# module.net
KiCad netlist of a schematic drawn in EAGLE
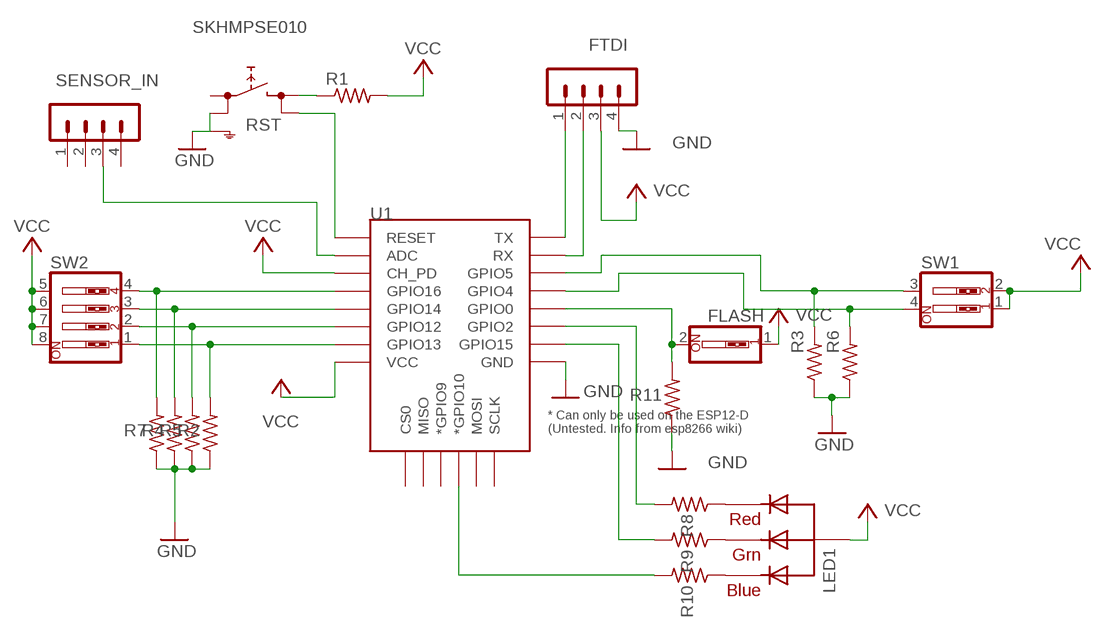
[diagram p0: schematic, sheet 1]

(export (version "E")
  (design (tool "Eeschema 10.0.6"))
  (components
    (comp (ref "FLASH")
      (value "SW_DIP-1")
      (footprint "eagle-import:EDG-01")
      (libsource (lib "eagle-import") (part "SW_DIP-1"))
    )
    (comp (ref "FTDI")
      (value "MA04-1")
      (footprint "eagle-import:MA04-1")
      (libsource (lib "eagle-import") (part "MA04-1"))
    )
    (comp (ref "LED1")
      (value "RGBLED_CA-5MM")
      (footprint "eagle-import:LED5MMRGB")
      (libsource (lib "eagle-import") (part "RGBLED_CA-5MM"))
    )
    (comp (ref "R1")
      (value "R-US_0207/12")
      (footprint "eagle-import:0207_12")
      (libsource (lib "eagle-import") (part "R-US_0207/12"))
    )
    (comp (ref "R2")
      (value "R-US_0207/12")
      (footprint "eagle-import:0207_12")
      (libsource (lib "eagle-import") (part "R-US_0207/12"))
    )
    (comp (ref "R3")
      (value "R-US_0207/12")
      (footprint "eagle-import:0207_12")
      (libsource (lib "eagle-import") (part "R-US_0207/12"))
    )
    (comp (ref "R4")
      (value "R-US_0207/12")
      (footprint "eagle-import:0207_12")
      (libsource (lib "eagle-import") (part "R-US_0207/12"))
    )
    (comp (ref "R5")
      (value "R-US_0207/12")
      (footprint "eagle-import:0207_12")
      (libsource (lib "eagle-import") (part "R-US_0207/12"))
    )
    (comp (ref "R6")
      (value "R-US_0207/12")
      (footprint "eagle-import:0207_12")
      (libsource (lib "eagle-import") (part "R-US_0207/12"))
    )
    (comp (ref "R7")
      (value "R-US_0207/12")
      (footprint "eagle-import:0207_12")
      (libsource (lib "eagle-import") (part "R-US_0207/12"))
    )
    (comp (ref "R8")
      (value "R-US_0207/12")
      (footprint "eagle-import:0207_12")
      (libsource (lib "eagle-import") (part "R-US_0207/12"))
    )
    (comp (ref "R9")
      (value "R-US_0207/12")
      (footprint "eagle-import:0207_12")
      (libsource (lib "eagle-import") (part "R-US_0207/12"))
    )
    (comp (ref "R10")
      (value "R-US_0207/12")
      (footprint "eagle-import:0207_12")
      (libsource (lib "eagle-import") (part "R-US_0207/12"))
    )
    (comp (ref "R11")
      (value "R-US_0207/12")
      (footprint "eagle-import:0207_12")
      (libsource (lib "eagle-import") (part "R-US_0207/12"))
    )
    (comp (ref "RST")
      (value "SKHMPSE010")
      (footprint "eagle-import:SKHMPXE010")
      (libsource (lib "eagle-import") (part "SKHMPE010S"))
    )
    (comp (ref "SENSOR_IN")
      (value "MA04-1")
      (footprint "eagle-import:MA04-1")
      (libsource (lib "eagle-import") (part "MA04-1"))
    )
    (comp (ref "SW1")
      (value "SW_DIP-2")
      (footprint "eagle-import:EDG-02")
      (libsource (lib "eagle-import") (part "SW_DIP-2"))
    )
    (comp (ref "SW2")
      (value "SW_DIP-4")
      (footprint "eagle-import:EDG-04")
      (libsource (lib "eagle-import") (part "SW_DIP-4"))
    )
    (comp (ref "U1")
      (value "ESP12ESMD")
      (footprint "eagle-import:ESP12E-SMD")
      (libsource (lib "eagle-import") (part "ESP12ESMD"))
    )
  )
  (nets
    (net (code "1") (name "GND") (class "Default")
      (node (ref "FTDI") (pin "4") (pinfunction "4_4") (pintype "passive"))
      (node (ref "R11") (pin "1") (pinfunction "1_1") (pintype "passive"))
      (node (ref "R2") (pin "1") (pinfunction "1_1") (pintype "passive"))
      (node (ref "R3") (pin "1") (pinfunction "1_1") (pintype "passive"))
      (node (ref "R4") (pin "1") (pinfunction "1_1") (pintype "passive"))
      (node (ref "R5") (pin "1") (pinfunction "1_1") (pintype "passive"))
      (node (ref "R6") (pin "1") (pinfunction "1_1") (pintype "passive"))
      (node (ref "R7") (pin "1") (pinfunction "1_1") (pintype "passive"))
      (node (ref "RST") (pin "2") (pinfunction "1.2_2") (pintype "passive"))
      (node (ref "RST") (pin "5") (pinfunction "SH_5") (pintype "passive"))
      (node (ref "U1") (pin "GND") (pinfunction "GND_GND") (pintype "bidirectional"))
    )
    (net (code "2") (name "Net-(FLASH-Pad2)") (class "Default")
      (node (ref "FLASH") (pin "2") (pinfunction "2_2") (pintype "passive"))
      (node (ref "R11") (pin "2") (pinfunction "2_2") (pintype "passive"))
      (node (ref "U1") (pin "GPIO0") (pinfunction "GPIO0_GPIO0") (pintype "bidirectional"))
    )
    (net (code "3") (name "Net-(LED1-BLUE)") (class "Default")
      (node (ref "LED1") (pin "4") (pinfunction "BLUE_4") (pintype "bidirectional"))
      (node (ref "R10") (pin "1") (pinfunction "1_1") (pintype "passive"))
    )
    (net (code "4") (name "Net-(LED1-GREEN)") (class "Default")
      (node (ref "LED1") (pin "3") (pinfunction "GREEN_3") (pintype "bidirectional"))
      (node (ref "R9") (pin "1") (pinfunction "1_1") (pintype "passive"))
    )
    (net (code "5") (name "Net-(LED1-RED)") (class "Default")
      (node (ref "LED1") (pin "1") (pinfunction "RED_1") (pintype "bidirectional"))
      (node (ref "R8") (pin "1") (pinfunction "1_1") (pintype "passive"))
    )
    (net (code "6") (name "Net-(R2-Pad2)") (class "Default")
      (node (ref "R2") (pin "2") (pinfunction "2_2") (pintype "passive"))
      (node (ref "SW2") (pin "1") (pinfunction "1_1") (pintype "passive"))
      (node (ref "U1") (pin "GPIO13") (pinfunction "GPIO13_GPIO13") (pintype "bidirectional"))
    )
    (net (code "7") (name "Net-(R3-Pad2)") (class "Default")
      (node (ref "R3") (pin "2") (pinfunction "2_2") (pintype "passive"))
      (node (ref "SW1") (pin "3") (pinfunction "3_3") (pintype "passive"))
      (node (ref "U1") (pin "GPIO5") (pinfunction "GPIO5_GPIO5") (pintype "bidirectional"))
    )
    (net (code "8") (name "Net-(R4-Pad2)") (class "Default")
      (node (ref "R4") (pin "2") (pinfunction "2_2") (pintype "passive"))
      (node (ref "SW2") (pin "3") (pinfunction "3_3") (pintype "passive"))
      (node (ref "U1") (pin "GPIO14") (pinfunction "GPIO14_GPIO14") (pintype "bidirectional"))
    )
    (net (code "9") (name "Net-(R5-Pad2)") (class "Default")
      (node (ref "R5") (pin "2") (pinfunction "2_2") (pintype "passive"))
      (node (ref "SW2") (pin "2") (pinfunction "2_2") (pintype "passive"))
      (node (ref "U1") (pin "GPIO12") (pinfunction "GPIO12_GPIO12") (pintype "bidirectional"))
    )
    (net (code "10") (name "Net-(R6-Pad2)") (class "Default")
      (node (ref "R6") (pin "2") (pinfunction "2_2") (pintype "passive"))
      (node (ref "SW1") (pin "4") (pinfunction "4_4") (pintype "passive"))
      (node (ref "U1") (pin "GPIO4") (pinfunction "GPIO4_GPIO4") (pintype "bidirectional"))
    )
    (net (code "11") (name "Net-(R7-Pad2)") (class "Default")
      (node (ref "R7") (pin "2") (pinfunction "2_2") (pintype "passive"))
      (node (ref "SW2") (pin "4") (pinfunction "4_4") (pintype "passive"))
      (node (ref "U1") (pin "GPIO16") (pinfunction "GPIO16_GPIO16") (pintype "bidirectional"))
    )
    (net (code "12") (name "Net-(R8-Pad2)") (class "Default")
      (node (ref "R8") (pin "2") (pinfunction "2_2") (pintype "passive"))
      (node (ref "U1") (pin "GPIO2") (pinfunction "GPIO2_GPIO2") (pintype "bidirectional"))
    )
    (net (code "13") (name "Net-(R9-Pad2)") (class "Default")
      (node (ref "R9") (pin "2") (pinfunction "2_2") (pintype "passive"))
      (node (ref "U1") (pin "GPIO15") (pinfunction "GPIO15_GPIO15") (pintype "bidirectional"))
    )
    (net (code "14") (name "Net-(RST-2.1)") (class "Default")
      (node (ref "R1") (pin "1") (pinfunction "1_1") (pintype "passive"))
      (node (ref "RST") (pin "3") (pinfunction "2.1_3") (pintype "passive"))
    )
    (net (code "15") (name "Net-(RST-2.2)") (class "Default")
      (node (ref "RST") (pin "4") (pinfunction "2.2_4") (pintype "passive"))
      (node (ref "U1") (pin "RESET") (pinfunction "RESET_RESET") (pintype "bidirectional"))
    )
    (net (code "16") (name "Net-(SENSOR_IN-Pad3)") (class "Default")
      (node (ref "SENSOR_IN") (pin "3") (pinfunction "3_3") (pintype "passive"))
      (node (ref "U1") (pin "ADC") (pinfunction "ADC_ADC") (pintype "bidirectional"))
    )
    (net (code "17") (name "Net-(U1-*GPIO10)") (class "Default")
      (node (ref "R10") (pin "2") (pinfunction "2_2") (pintype "passive"))
      (node (ref "U1") (pin "GPIO10") (pinfunction "*GPIO10_GPIO10") (pintype "bidirectional"))
    )
    (net (code "18") (name "Net-(U1-RX)") (class "Default")
      (node (ref "FTDI") (pin "2") (pinfunction "2_2") (pintype "passive"))
      (node (ref "U1") (pin "RXD0") (pinfunction "RX_RXD0") (pintype "bidirectional"))
    )
    (net (code "19") (name "Net-(U1-TX)") (class "Default")
      (node (ref "FTDI") (pin "1") (pinfunction "1_1") (pintype "passive"))
      (node (ref "U1") (pin "TXD0") (pinfunction "TX_TXD0") (pintype "bidirectional"))
    )
    (net (code "20") (name "VCC") (class "Default")
      (node (ref "FLASH") (pin "1") (pinfunction "1_1") (pintype "passive"))
      (node (ref "FTDI") (pin "3") (pinfunction "3_3") (pintype "passive"))
      (node (ref "LED1") (pin "2") (pinfunction "VCC_2") (pintype "bidirectional"))
      (node (ref "R1") (pin "2") (pinfunction "2_2") (pintype "passive"))
      (node (ref "SW1") (pin "1") (pinfunction "1_1") (pintype "passive"))
      (node (ref "SW1") (pin "2") (pinfunction "2_2") (pintype "passive"))
      (node (ref "SW2") (pin "5") (pinfunction "5_5") (pintype "passive"))
      (node (ref "SW2") (pin "6") (pinfunction "6_6") (pintype "passive"))
      (node (ref "SW2") (pin "7") (pinfunction "7_7") (pintype "passive"))
      (node (ref "SW2") (pin "8") (pinfunction "8_8") (pintype "passive"))
      (node (ref "U1") (pin "CH_PD") (pinfunction "CH_PD_CH_PD") (pintype "bidirectional"))
      (node (ref "U1") (pin "VCC") (pinfunction "VCC_VCC") (pintype "bidirectional"))
    )
    (net (code "21") (name "unconnected-(RST-1.1-Pad1)") (class "Default")
      (node (ref "RST") (pin "1") (pinfunction "1.1_1") (pintype "passive"))
    )
    (net (code "22") (name "unconnected-(SENSOR_IN-Pad1)") (class "Default")
      (node (ref "SENSOR_IN") (pin "1") (pinfunction "1_1") (pintype "passive"))
    )
    (net (code "23") (name "unconnected-(SENSOR_IN-Pad2)") (class "Default")
      (node (ref "SENSOR_IN") (pin "2") (pinfunction "2_2") (pintype "passive"))
    )
    (net (code "24") (name "unconnected-(SENSOR_IN-Pad4)") (class "Default")
      (node (ref "SENSOR_IN") (pin "4") (pinfunction "4_4") (pintype "passive"))
    )
    (net (code "25") (name "unconnected-(U1-*GPIO9-PadGPIO9)") (class "Default")
      (node (ref "U1") (pin "GPIO9") (pinfunction "*GPIO9_GPIO9") (pintype "bidirectional"))
    )
    (net (code "26") (name "unconnected-(U1-PadCS0)") (class "Default")
      (node (ref "U1") (pin "CS0") (pinfunction "CS0_CS0") (pintype "bidirectional"))
    )
    (net (code "27") (name "unconnected-(U1-PadMISO)") (class "Default")
      (node (ref "U1") (pin "MISO") (pinfunction "MISO_MISO") (pintype "bidirectional"))
    )
    (net (code "28") (name "unconnected-(U1-PadMOSI)") (class "Default")
      (node (ref "U1") (pin "MOSI") (pinfunction "MOSI_MOSI") (pintype "bidirectional"))
    )
    (net (code "29") (name "unconnected-(U1-PadSCLK)") (class "Default")
      (node (ref "U1") (pin "SCLK") (pinfunction "SCLK_SCLK") (pintype "bidirectional"))
    )
  )
)
